# quadcopter.net
KiCad netlist of a schematic drawn in EAGLE
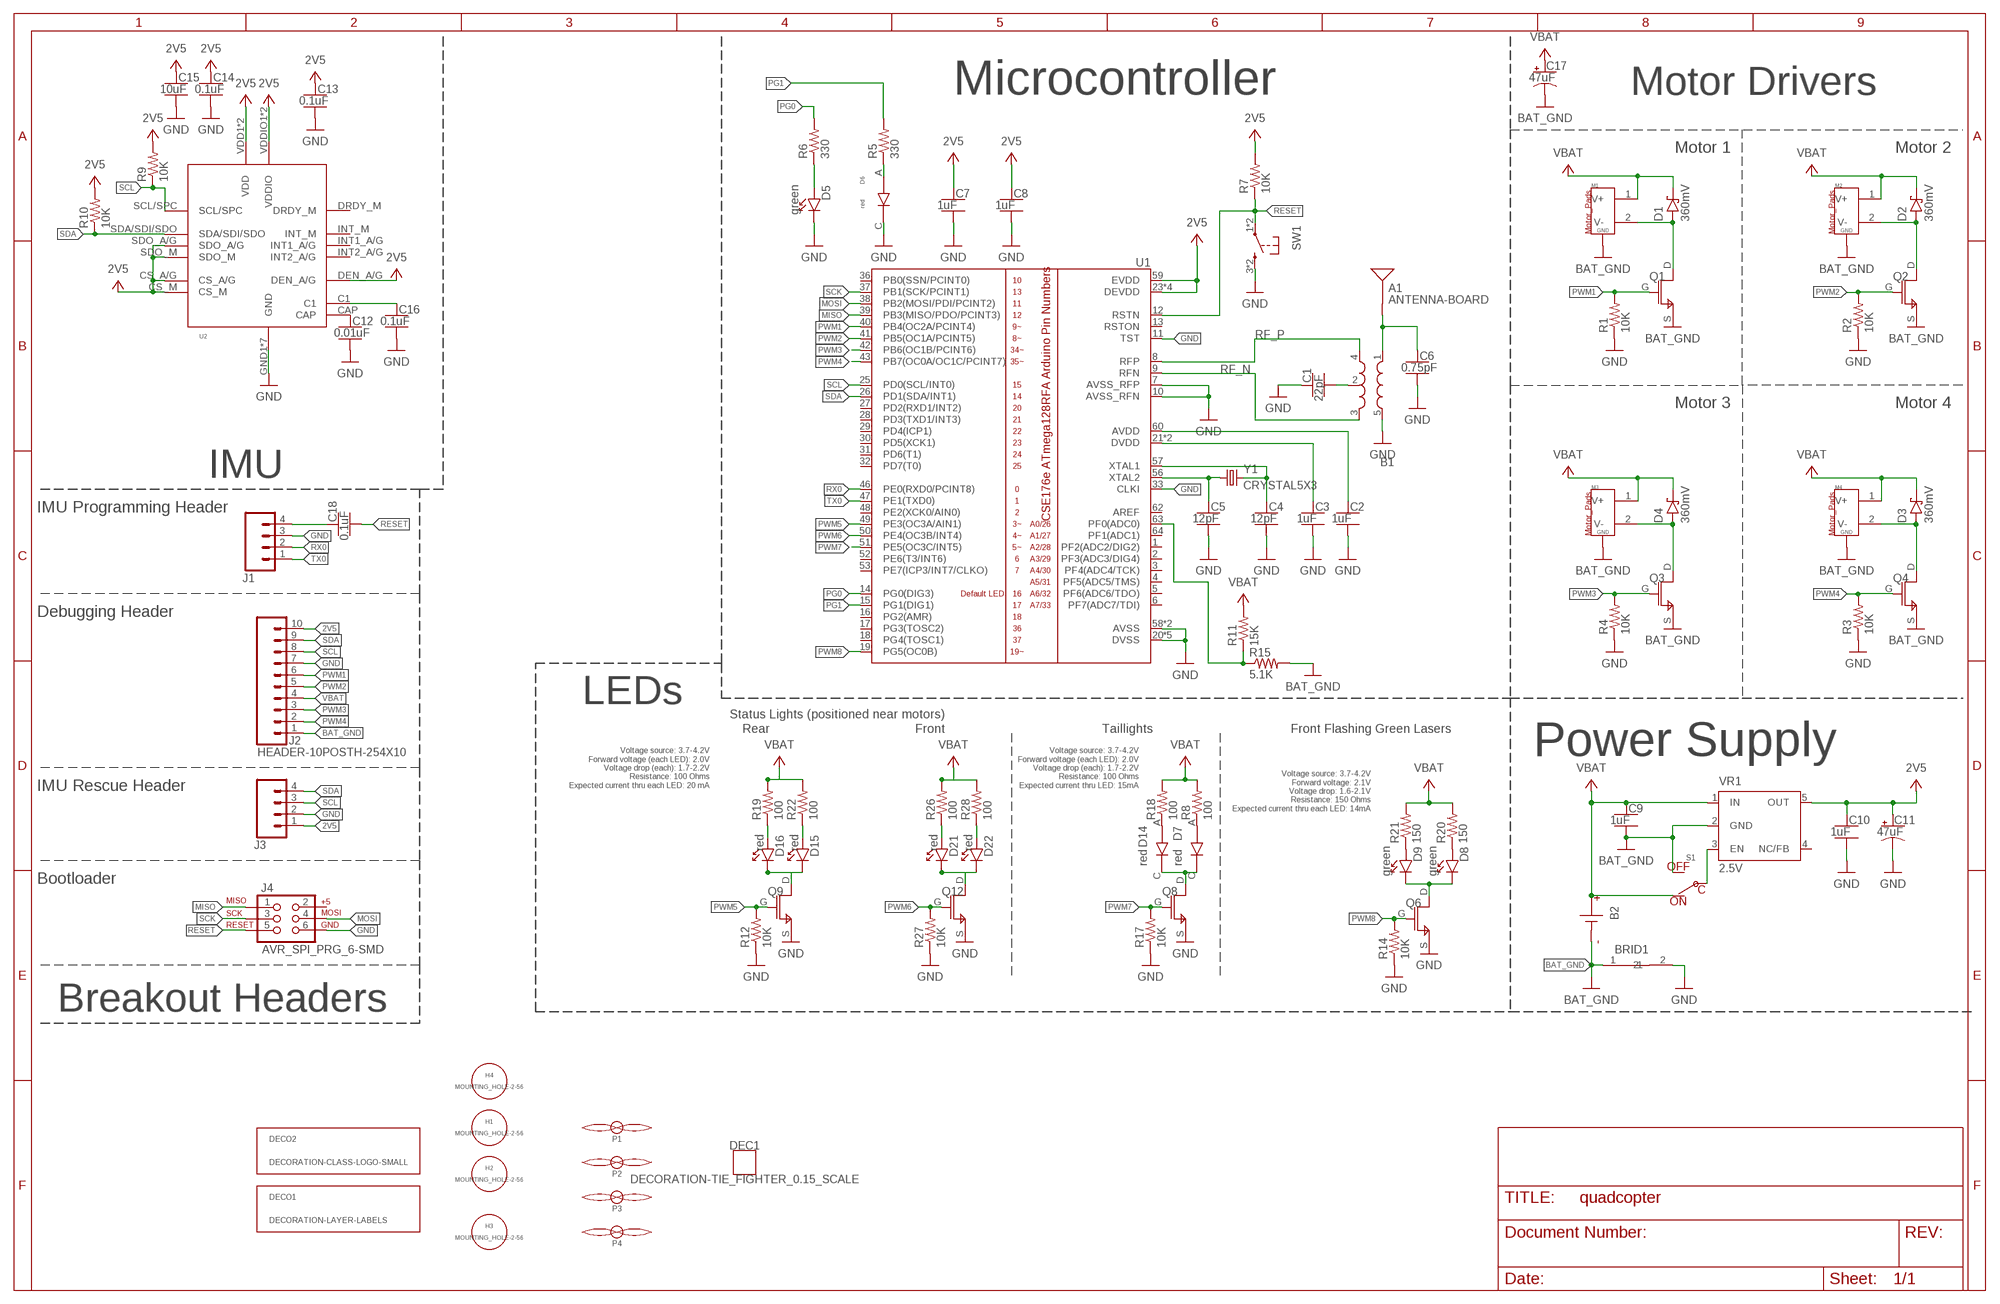
[diagram p0: schematic, sheet 1]

(export (version "E")
  (design (tool "Eeschema 10.0.6"))
  (components
    (comp (ref "A1")
      (value "ANTENNA-BOARD")
      (footprint "eagle-import:ANT_PCB_2.4GHZ_NRF8001_1.6MM_1OZ")
      (fields (field (name "MFR") "NA"))
      (libsource (lib "eagle-import") (part "ANTENNA-BOARD"))
    )
    (comp (ref "B1")
      (value "BALUN0805")
      (footprint "eagle-import:BALUN")
      (fields (field (name "MFR") "Wurth Electronics Inc.") (field (name "MPN") "748421245"))
      (libsource (lib "eagle-import") (part "BALUN0805"))
    )
    (comp (ref "B2")
      (value "BATTERY-SMD-TH")
      (footprint "eagle-import:BATTERY-COMBO")
      (libsource (lib "eagle-import") (part "BATTERY-SMD-TH"))
    )
    (comp (ref "BRID1")
      (value "NET_BRIDGE_5X5")
      (footprint "eagle-import:NET_BRIDGE_5X5")
      (libsource (lib "eagle-import") (part "NET_BRIDGE_5X5"))
    )
    (comp (ref "C1")
      (value "22pF")
      (footprint "eagle-import:CAPC2012X140_HS")
      (fields (field (name "MFR") "Murata Electronics") (field (name "MPN") "GRM21A5C2E220JW01D"))
      (libsource (lib "eagle-import") (part "CAPACITOR-NP_SMD-2012-0805_CERAMIC-22PF"))
    )
    (comp (ref "C2")
      (value "1uF")
      (footprint "eagle-import:CAPC2012X140_HS")
      (fields (field (name "MFR") "Taiyo Yuden") (field (name "MPN") "TMK212B7105KG-T"))
      (libsource (lib "eagle-import") (part "CAPACITOR-NP_SMD-2012-0805_CERAMIC-1UF"))
    )
    (comp (ref "C3")
      (value "1uF")
      (footprint "eagle-import:CAPC2012X140_HS")
      (fields (field (name "MFR") "Taiyo Yuden") (field (name "MPN") "TMK212B7105KG-T"))
      (libsource (lib "eagle-import") (part "CAPACITOR-NP_SMD-2012-0805_CERAMIC-1UF"))
    )
    (comp (ref "C4")
      (value "12pF")
      (footprint "eagle-import:CAPC2012X140_HS")
      (fields (field (name "MFR") "Murata Electronics") (field (name "MPN") "GRM21A5C2E120JW01D"))
      (libsource (lib "eagle-import") (part "CAPACITOR-NP_SMD-2012-0805_CERAMIC-12PF"))
    )
    (comp (ref "C5")
      (value "12pF")
      (footprint "eagle-import:CAPC2012X140_HS")
      (fields (field (name "MFR") "Murata Electronics") (field (name "MPN") "GRM21A5C2E120JW01D"))
      (libsource (lib "eagle-import") (part "CAPACITOR-NP_SMD-2012-0805_CERAMIC-12PF"))
    )
    (comp (ref "C6")
      (value "0.75pF")
      (footprint "eagle-import:CAPC2012X140_HS")
      (fields (field (name "MFR") "Murata Electronics") (field (name "MPN") "GQM2195C2AR75CB01D"))
      (libsource (lib "eagle-import") (part "CAPACITOR-NP_SMD-2012-0805_CERAMIC-0.75PF"))
    )
    (comp (ref "C7")
      (value "1uF")
      (footprint "eagle-import:CAPC2012X140_HS")
      (fields (field (name "MFR") "Taiyo Yuden") (field (name "MPN") "TMK212B7105KG-T"))
      (libsource (lib "eagle-import") (part "CAPACITOR-NP_SMD-2012-0805_CERAMIC-1UF"))
    )
    (comp (ref "C8")
      (value "1uF")
      (footprint "eagle-import:CAPC2012X140_HS")
      (fields (field (name "MFR") "Taiyo Yuden") (field (name "MPN") "TMK212B7105KG-T"))
      (libsource (lib "eagle-import") (part "CAPACITOR-NP_SMD-2012-0805_CERAMIC-1UF"))
    )
    (comp (ref "C9")
      (value "1uF")
      (footprint "eagle-import:CAPC2012X140_HS")
      (fields (field (name "MFR") "Taiyo Yuden") (field (name "MPN") "TMK212B7105KG-T"))
      (libsource (lib "eagle-import") (part "CAPACITOR-NP_SMD-2012-0805_CERAMIC-1UF"))
    )
    (comp (ref "C10")
      (value "1uF")
      (footprint "eagle-import:CAPC2012X140_HS")
      (fields (field (name "MFR") "Taiyo Yuden") (field (name "MPN") "TMK212B7105KG-T"))
      (libsource (lib "eagle-import") (part "CAPACITOR-NP_SMD-2012-0805_CERAMIC-1UF"))
    )
    (comp (ref "C11")
      (value "47uF")
      (footprint "eagle-import:CAPMP3216X180")
      (fields (field (name "MFR") "AVX Corporation") (field (name "MPN") "TAJA476K006SNJV"))
      (libsource (lib "eagle-import") (part "CAPACITOR-POL_47UF-SMD-1206-TAJA"))
    )
    (comp (ref "C12")
      (value "0.01uF")
      (footprint "eagle-import:CAPC2012X140_HS")
      (fields (field (name "MFR") "Knowles Syfer") (field (name "MPN") "0805J0500104KJT"))
      (libsource (lib "eagle-import") (part "CAPACITOR-NP_SMD-2012-0805_CERAMIC-0.01UF"))
    )
    (comp (ref "C13")
      (value "0.1uF")
      (footprint "eagle-import:CAPC2012X140_HS")
      (fields (field (name "MFR") "TDK Corporation") (field (name "MPN") "C2012X7R2A104K125AA"))
      (libsource (lib "eagle-import") (part "CAPACITOR-NP_SMD-2012-0805_CERAMIC-0.1UF"))
    )
    (comp (ref "C14")
      (value "0.1uF")
      (footprint "eagle-import:CAPC2012X140_HS")
      (fields (field (name "MFR") "TDK Corporation") (field (name "MPN") "C2012X7R2A104K125AA"))
      (libsource (lib "eagle-import") (part "CAPACITOR-NP_SMD-2012-0805_CERAMIC-0.1UF"))
    )
    (comp (ref "C15")
      (value "10uF")
      (footprint "eagle-import:CAPC2012X140_HS")
      (fields (field (name "MFR") "TDK") (field (name "MPN") "C2012X5R1E106K125AB"))
      (libsource (lib "eagle-import") (part "CAPACITOR-NP_SMD-2012-0805_CERAMIC-10UF"))
    )
    (comp (ref "C16")
      (value "0.1uF")
      (footprint "eagle-import:CAPC2012X140_HS")
      (fields (field (name "MFR") "TDK Corporation") (field (name "MPN") "C2012X7R2A104K125AA"))
      (libsource (lib "eagle-import") (part "CAPACITOR-NP_SMD-2012-0805_CERAMIC-0.1UF"))
    )
    (comp (ref "C17")
      (value "47uF")
      (footprint "eagle-import:CAPMP3216X180")
      (fields (field (name "MFR") "AVX Corporation") (field (name "MPN") "TAJA476K006SNJV"))
      (libsource (lib "eagle-import") (part "CAPACITOR-POL_47UF-SMD-1206-TAJA"))
    )
    (comp (ref "C18")
      (value "0.1uF")
      (footprint "eagle-import:CAPC2012X140_HS")
      (fields (field (name "MFR") "TDK Corporation") (field (name "MPN") "C2012X7R2A104K125AA"))
      (libsource (lib "eagle-import") (part "CAPACITOR-NP_SMD-2012-0805_CERAMIC-0.1UF"))
    )
    (comp (ref "D1")
      (value "360mV")
      (footprint "eagle-import:SODFL3516X96")
      (fields
        (field (name "MFR") "Toshiba Semiconductor and Storage")
        (field (name "MPN") "CRS08(TE85L,Q,M)")
      )
      (libsource (lib "eagle-import") (part "DIODE-SCHOTTKY_-SMD-SOD123"))
    )
    (comp (ref "D2")
      (value "360mV")
      (footprint "eagle-import:SODFL3516X96")
      (fields
        (field (name "MFR") "Toshiba Semiconductor and Storage")
        (field (name "MPN") "CRS08(TE85L,Q,M)")
      )
      (libsource (lib "eagle-import") (part "DIODE-SCHOTTKY_-SMD-SOD123"))
    )
    (comp (ref "D3")
      (value "360mV")
      (footprint "eagle-import:SODFL3516X96")
      (fields
        (field (name "MFR") "Toshiba Semiconductor and Storage")
        (field (name "MPN") "CRS08(TE85L,Q,M)")
      )
      (libsource (lib "eagle-import") (part "DIODE-SCHOTTKY_-SMD-SOD123"))
    )
    (comp (ref "D4")
      (value "360mV")
      (footprint "eagle-import:SODFL3516X96")
      (fields
        (field (name "MFR") "Toshiba Semiconductor and Storage")
        (field (name "MPN") "CRS08(TE85L,Q,M)")
      )
      (libsource (lib "eagle-import") (part "DIODE-SCHOTTKY_-SMD-SOD123"))
    )
    (comp (ref "D5")
      (value "green")
      (footprint "eagle-import:LEDSC125X200X120-2_HS")
      (fields (field (name "MFR") "Lite-On Inc") (field (name "MPN") "LTST-C170GKT"))
      (libsource (lib "eagle-import") (part "DIODE-LED_SMD-2012-0805-GREEN"))
    )
    (comp (ref "D6")
      (value "red")
      (footprint "eagle-import:LTST-C170EKT")
      (libsource (lib "eagle-import") (part "LED_RED-LTST-C170EKT"))
    )
    (comp (ref "D7")
      (value "red")
      (footprint "eagle-import:LTST-C170EKT")
      (libsource (lib "eagle-import") (part "LED_RED-LTST-C170EKT"))
    )
    (comp (ref "D8")
      (value "green")
      (footprint "eagle-import:LEDSC125X200X120-2_HS")
      (fields (field (name "MFR") "Lite-On Inc") (field (name "MPN") "LTST-C170GKT"))
      (libsource (lib "eagle-import") (part "DIODE-LED_SMD-2012-0805-GREEN"))
    )
    (comp (ref "D9")
      (value "green")
      (footprint "eagle-import:LEDSC125X200X120-2_HS")
      (fields (field (name "MFR") "Lite-On Inc") (field (name "MPN") "LTST-C170GKT"))
      (libsource (lib "eagle-import") (part "DIODE-LED_SMD-2012-0805-GREEN"))
    )
    (comp (ref "D14")
      (value "red")
      (footprint "eagle-import:LTST-C170EKT")
      (libsource (lib "eagle-import") (part "LED_RED-LTST-C170EKT"))
    )
    (comp (ref "D15")
      (value "red")
      (footprint "eagle-import:1206_LED_REVERSE")
      (libsource (lib "eagle-import") (part "LED-350-2312-1-ND-REVERSE"))
    )
    (comp (ref "D16")
      (value "red")
      (footprint "eagle-import:1206_LED_REVERSE")
      (libsource (lib "eagle-import") (part "LED-350-2312-1-ND-REVERSE"))
    )
    (comp (ref "D21")
      (value "red")
      (footprint "eagle-import:1206_LED_REVERSE")
      (libsource (lib "eagle-import") (part "LED-350-2312-1-ND-REVERSE"))
    )
    (comp (ref "D22")
      (value "red")
      (footprint "eagle-import:1206_LED_REVERSE")
      (libsource (lib "eagle-import") (part "LED-350-2312-1-ND-REVERSE"))
    )
    (comp (ref "DEC1")
      (value "DECORATION-TIE_FIGHTER_0.15_SCALE")
      (footprint "eagle-import:TIE_FIGHTER_0.15_SCALE")
      (libsource (lib "eagle-import") (part "DECORATION-TIE_FIGHTER_0.15_SCALE"))
    )
    (comp (ref "DECO1")
      (value "DECORATION-LAYER-LABELS")
      (footprint "eagle-import:LAYER_LABELS")
      (libsource (lib "eagle-import") (part "DECORATION-LAYER-LABELS"))
    )
    (comp (ref "DECO2")
      (value "DECORATION-CLASS-LOGO-SMALL")
      (footprint "eagle-import:QUADCLASS_LOGO_SMALL")
      (libsource (lib "eagle-import") (part "DECORATION-CLASS-LOGO-SMALL"))
    )
    (comp (ref "H1")
      (value "MOUNTING_HOLE-2-56")
      (footprint "eagle-import:2-56-MOUNTING-HOLE-NO-METAL")
      (libsource (lib "eagle-import") (part "MOUNTING_HOLE-2-56"))
    )
    (comp (ref "H2")
      (value "MOUNTING_HOLE-2-56")
      (footprint "eagle-import:2-56-MOUNTING-HOLE-NO-METAL")
      (libsource (lib "eagle-import") (part "MOUNTING_HOLE-2-56"))
    )
    (comp (ref "H3")
      (value "MOUNTING_HOLE-2-56")
      (footprint "eagle-import:2-56-MOUNTING-HOLE-NO-METAL")
      (libsource (lib "eagle-import") (part "MOUNTING_HOLE-2-56"))
    )
    (comp (ref "H4")
      (value "MOUNTING_HOLE-2-56")
      (footprint "eagle-import:2-56-MOUNTING-HOLE-NO-METAL")
      (libsource (lib "eagle-import") (part "MOUNTING_HOLE-2-56"))
    )
    (comp (ref "J1")
      (value "HEADER-4POS-0.1IN-FEMALE-SMD-BOTTOM-ENTRY")
      (footprint "eagle-import:HEADER-1X4-BOTTOM-ENTRY")
      (fields (field (name "MFR") "TE Connectivity AMP Connectors") (field (name "MPN") "1241152-4"))
      (libsource (lib "eagle-import") (part "HEADER-4POS-0.1IN-FEMALE-SMD-BOTTOM-ENTRY"))
    )
    (comp (ref "J2")
      (value "HEADER-10POSTH-254X10")
      (footprint "eagle-import:HDRV10W63P254_10X1_2540X254H838_HS")
      (fields (field (name "MFR") "Amphenol FCI") (field (name "MPN") "68000-110HLF"))
      (libsource (lib "eagle-import") (part "HEADER-10POSTH-254X10"))
    )
    (comp (ref "J3")
      (value "HEADER-4POS-0.1IN-FEMALE")
      (footprint "eagle-import:HDRVR4W80P254_1X4_1066X254X850B")
      (libsource (lib "eagle-import") (part "HEADER-4POS-0.1IN-FEMALE"))
    )
    (comp (ref "J4")
      (value "AVR_SPI_PRG_6-SMD")
      (footprint "eagle-import:2X3-SMD")
      (fields (field (name "MFR") "Amphenol ICC (FCI)") (field (name "MPN") "95278-101A06LF"))
      (libsource (lib "eagle-import") (part "AVR_SPI_PRG_6-SMD"))
    )
    (comp (ref "M1")
      (value "MOTOR_PADS_GND-MOLEX-SMD")
      (footprint "eagle-import:MOLEX-0532610271")
      (fields (field (name "MFR") "Molex") (field (name "MPN") "532610271"))
      (libsource (lib "eagle-import") (part "MOTOR_PADS_GND-MOLEX-SMD"))
    )
    (comp (ref "M2")
      (value "MOTOR_PADS_GND-MOLEX-SMD")
      (footprint "eagle-import:MOLEX-0532610271")
      (fields (field (name "MFR") "Molex") (field (name "MPN") "532610271"))
      (libsource (lib "eagle-import") (part "MOTOR_PADS_GND-MOLEX-SMD"))
    )
    (comp (ref "M3")
      (value "MOTOR_PADS_GND-MOLEX-SMD")
      (footprint "eagle-import:MOLEX-0532610271")
      (fields (field (name "MFR") "Molex") (field (name "MPN") "532610271"))
      (libsource (lib "eagle-import") (part "MOTOR_PADS_GND-MOLEX-SMD"))
    )
    (comp (ref "M4")
      (value "MOTOR_PADS_GND-MOLEX-SMD")
      (footprint "eagle-import:MOLEX-0532610271")
      (fields (field (name "MFR") "Molex") (field (name "MPN") "532610271"))
      (libsource (lib "eagle-import") (part "MOTOR_PADS_GND-MOLEX-SMD"))
    )
    (comp (ref "P1")
      (value "PROPELLOR-45MM")
      (footprint "eagle-import:MOTOR_AND_PROP")
      (libsource (lib "eagle-import") (part "PROPELLOR-45MM"))
    )
    (comp (ref "P2")
      (value "PROPELLOR-45MM")
      (footprint "eagle-import:MOTOR_AND_PROP")
      (libsource (lib "eagle-import") (part "PROPELLOR-45MM"))
    )
    (comp (ref "P3")
      (value "PROPELLOR-45MM")
      (footprint "eagle-import:MOTOR_AND_PROP")
      (libsource (lib "eagle-import") (part "PROPELLOR-45MM"))
    )
    (comp (ref "P4")
      (value "PROPELLOR-45MM")
      (footprint "eagle-import:MOTOR_AND_PROP")
      (libsource (lib "eagle-import") (part "PROPELLOR-45MM"))
    )
    (comp (ref "Q1")
      (value "N-MOSFET-SI2302DS")
      (footprint "eagle-import:SI2302DS")
      (libsource (lib "eagle-import") (part "N-MOSFET-SI2302DS"))
    )
    (comp (ref "Q2")
      (value "N-MOSFET-SI2302DS")
      (footprint "eagle-import:SI2302DS")
      (libsource (lib "eagle-import") (part "N-MOSFET-SI2302DS"))
    )
    (comp (ref "Q3")
      (value "N-MOSFET-SI2302DS")
      (footprint "eagle-import:SI2302DS")
      (libsource (lib "eagle-import") (part "N-MOSFET-SI2302DS"))
    )
    (comp (ref "Q4")
      (value "N-MOSFET-SI2302DS")
      (footprint "eagle-import:SI2302DS")
      (libsource (lib "eagle-import") (part "N-MOSFET-SI2302DS"))
    )
    (comp (ref "Q6")
      (value "N-MOSFET-SI2302DS")
      (footprint "eagle-import:SI2302DS")
      (libsource (lib "eagle-import") (part "N-MOSFET-SI2302DS"))
    )
    (comp (ref "Q8")
      (value "N-MOSFET-SI2302DS")
      (footprint "eagle-import:SI2302DS")
      (libsource (lib "eagle-import") (part "N-MOSFET-SI2302DS"))
    )
    (comp (ref "Q9")
      (value "N-MOSFET-SI2302DS")
      (footprint "eagle-import:SI2302DS")
      (libsource (lib "eagle-import") (part "N-MOSFET-SI2302DS"))
    )
    (comp (ref "Q12")
      (value "N-MOSFET-SI2302DS")
      (footprint "eagle-import:SI2302DS")
      (libsource (lib "eagle-import") (part "N-MOSFET-SI2302DS"))
    )
    (comp (ref "R1")
      (value "10K")
      (footprint "eagle-import:RESC2012X60_HS")
      (fields (field (name "MFR") "Yageo") (field (name "MPN") "RC0805JR-0710KL"))
      (libsource (lib "eagle-import") (part "RESISTOR_SMD-2012-0805-10K"))
    )
    (comp (ref "R2")
      (value "10K")
      (footprint "eagle-import:RESC2012X60_HS")
      (fields (field (name "MFR") "Yageo") (field (name "MPN") "RC0805JR-0710KL"))
      (libsource (lib "eagle-import") (part "RESISTOR_SMD-2012-0805-10K"))
    )
    (comp (ref "R3")
      (value "10K")
      (footprint "eagle-import:RESC2012X60_HS")
      (fields (field (name "MFR") "Yageo") (field (name "MPN") "RC0805JR-0710KL"))
      (libsource (lib "eagle-import") (part "RESISTOR_SMD-2012-0805-10K"))
    )
    (comp (ref "R4")
      (value "10K")
      (footprint "eagle-import:RESC2012X60_HS")
      (fields (field (name "MFR") "Yageo") (field (name "MPN") "RC0805JR-0710KL"))
      (libsource (lib "eagle-import") (part "RESISTOR_SMD-2012-0805-10K"))
    )
    (comp (ref "R5")
      (value "330")
      (footprint "eagle-import:RESC2012X60_HS")
      (fields (field (name "MFR") "Yageo") (field (name "MPN") "RC0805JR-07330RL"))
      (libsource (lib "eagle-import") (part "RESISTOR_SMD-2012-0805-330"))
    )
    (comp (ref "R6")
      (value "330")
      (footprint "eagle-import:RESC2012X60_HS")
      (fields (field (name "MFR") "Yageo") (field (name "MPN") "RC0805JR-07330RL"))
      (libsource (lib "eagle-import") (part "RESISTOR_SMD-2012-0805-330"))
    )
    (comp (ref "R7")
      (value "10K")
      (footprint "eagle-import:RESC2012X60_HS")
      (fields (field (name "MFR") "Yageo") (field (name "MPN") "RC0805JR-0710KL"))
      (libsource (lib "eagle-import") (part "RESISTOR_SMD-2012-0805-10K"))
    )
    (comp (ref "R8")
      (value "100")
      (footprint "eagle-import:RESC2012X60_HS")
      (fields (field (name "MFR") "Yageo") (field (name "MPN") "RC0805JR-07100RL"))
      (libsource (lib "eagle-import") (part "RESISTOR_SMD-2012-0805-100"))
    )
    (comp (ref "R9")
      (value "10K")
      (footprint "eagle-import:RESC2012X60_HS")
      (fields (field (name "MFR") "Yageo") (field (name "MPN") "RC0805JR-0710KL"))
      (libsource (lib "eagle-import") (part "RESISTOR_SMD-2012-0805-10K"))
    )
    (comp (ref "R10")
      (value "10K")
      (footprint "eagle-import:RESC2012X60_HS")
      (fields (field (name "MFR") "Yageo") (field (name "MPN") "RC0805JR-0710KL"))
      (libsource (lib "eagle-import") (part "RESISTOR_SMD-2012-0805-10K"))
    )
    (comp (ref "R11")
      (value "15K")
      (footprint "eagle-import:RESC2012X60_HS")
      (libsource (lib "eagle-import") (part "RESISTOR_SMD-2012-0805-15K"))
    )
    (comp (ref "R12")
      (value "10K")
      (footprint "eagle-import:RESC2012X60_HS")
      (fields (field (name "MFR") "Yageo") (field (name "MPN") "RC0805JR-0710KL"))
      (libsource (lib "eagle-import") (part "RESISTOR_SMD-2012-0805-10K"))
    )
    (comp (ref "R14")
      (value "10K")
      (footprint "eagle-import:RESC2012X60_HS")
      (fields (field (name "MFR") "Yageo") (field (name "MPN") "RC0805JR-0710KL"))
      (libsource (lib "eagle-import") (part "RESISTOR_SMD-2012-0805-10K"))
    )
    (comp (ref "R15")
      (value "5.1K")
      (footprint "eagle-import:RESC2012X60_HS")
      (fields (field (name "MFR") "Yageo") (field (name "MPN") "RC0805JR-075K1L"))
      (libsource (lib "eagle-import") (part "RESISTOR_SMD-2012-0805-5.1K"))
    )
    (comp (ref "R17")
      (value "10K")
      (footprint "eagle-import:RESC2012X60_HS")
      (fields (field (name "MFR") "Yageo") (field (name "MPN") "RC0805JR-0710KL"))
      (libsource (lib "eagle-import") (part "RESISTOR_SMD-2012-0805-10K"))
    )
    (comp (ref "R18")
      (value "100")
      (footprint "eagle-import:RESC2012X60_HS")
      (fields (field (name "MFR") "Yageo") (field (name "MPN") "RC0805JR-07100RL"))
      (libsource (lib "eagle-import") (part "RESISTOR_SMD-2012-0805-100"))
    )
    (comp (ref "R19")
      (value "100")
      (footprint "eagle-import:RESC2012X60_HS")
      (fields (field (name "MFR") "Yageo") (field (name "MPN") "RC0805JR-07100RL"))
      (libsource (lib "eagle-import") (part "RESISTOR_SMD-2012-0805-100"))
    )
    (comp (ref "R20")
      (value "150")
      (footprint "eagle-import:RESC2012X60_HS")
      (libsource (lib "eagle-import") (part "RESISTOR_SMD-2012-0805-150"))
    )
    (comp (ref "R21")
      (value "150")
      (footprint "eagle-import:RESC2012X60_HS")
      (libsource (lib "eagle-import") (part "RESISTOR_SMD-2012-0805-150"))
    )
    (comp (ref "R22")
      (value "100")
      (footprint "eagle-import:RESC2012X60_HS")
      (fields (field (name "MFR") "Yageo") (field (name "MPN") "RC0805JR-07100RL"))
      (libsource (lib "eagle-import") (part "RESISTOR_SMD-2012-0805-100"))
    )
    (comp (ref "R26")
      (value "100")
      (footprint "eagle-import:RESC2012X60_HS")
      (fields (field (name "MFR") "Yageo") (field (name "MPN") "RC0805JR-07100RL"))
      (libsource (lib "eagle-import") (part "RESISTOR_SMD-2012-0805-100"))
    )
    (comp (ref "R27")
      (value "10K")
      (footprint "eagle-import:RESC2012X60_HS")
      (fields (field (name "MFR") "Yageo") (field (name "MPN") "RC0805JR-0710KL"))
      (libsource (lib "eagle-import") (part "RESISTOR_SMD-2012-0805-10K"))
    )
    (comp (ref "R28")
      (value "100")
      (footprint "eagle-import:RESC2012X60_HS")
      (fields (field (name "MFR") "Yageo") (field (name "MPN") "RC0805JR-07100RL"))
      (libsource (lib "eagle-import") (part "RESISTOR_SMD-2012-0805-100"))
    )
    (comp (ref "S1")
      (value "POWER-SWITCH-MFS201N-9-Z-SMD-EDGE")
      (footprint "eagle-import:JS102011SAQN")
      (fields (field (name "MFR") "C&K") (field (name "MPN") "JS102011SAQN"))
      (libsource (lib "eagle-import") (part "POWER-SWITCH-MFS201N-9-Z-SMD-EDGE"))
    )
    (comp (ref "SW1")
      (value "PUSHBUTTON_-4.5X4.5")
      (footprint "eagle-import:4.5MM_TACTILE_SWITCH_TL3305AF160QG")
      (fields (field (name "MFR") "E-Switch") (field (name "MPN") "TL3305AF160QG"))
      (libsource (lib "eagle-import") (part "PUSHBUTTON_-4.5X4.5"))
    )
    (comp (ref "U1")
      (value "ATMEGA128RFA1")
      (footprint "eagle-import:QFN-64")
      (fields (field (name "MFR") "Microchip Technology") (field (name "MPN") "ATMEGA128RFA1-ZU"))
      (libsource (lib "eagle-import") (part "ATMEGA128RFA1"))
    )
    (comp (ref "U2")
      (value "IMU_LSM9DS1-LSM9DS1")
      (footprint "eagle-import:LSM9DS1")
      (libsource (lib "eagle-import") (part "IMU_LSM9DS1-LSM9DS1"))
    )
    (comp (ref "VR1")
      (value "2.5V")
      (footprint "eagle-import:SOT23-DBV")
      (fields (field (name "MFR") "Texas Instruments") (field (name "MPN") "LP3985IM5X-2.5/NOPB"))
      (libsource (lib "eagle-import") (part "TPS73633-DBVT2.5V"))
    )
    (comp (ref "Y1")
      (value "CRYSTAL5X3")
      (footprint "eagle-import:CRYSTAL-SMD-5X3")
      (fields (field (name "MFR") "Abracon LLC") (field (name "MPN") "ABM3B-16.000MHZ-B2-T"))
      (libsource (lib "eagle-import") (part "CRYSTAL5X3"))
    )
  )
  (nets
    (net (code "1") (name "/RF_N") (class "Default")
      (node (ref "B1") (pin "3") (pinfunction "OUT2_3") (pintype "bidirectional"))
      (node (ref "U1") (pin "9") (pinfunction "RFN_9") (pintype "bidirectional"))
    )
    (net (code "2") (name "/RF_P") (class "Default")
      (node (ref "B1") (pin "4") (pinfunction "OUT1_4") (pintype "bidirectional"))
      (node (ref "U1") (pin "8") (pinfunction "RFP_8") (pintype "bidirectional"))
    )
    (net (code "3") (name "2V5") (class "Default")
      (node (ref "C10") (pin "1") (pinfunction "1_1") (pintype "passive"))
      (node (ref "C11") (pin "1") (pinfunction "+_1") (pintype "passive"))
      (node (ref "C13") (pin "1") (pinfunction "1_1") (pintype "passive"))
      (node (ref "C14") (pin "1") (pinfunction "1_1") (pintype "passive"))
      (node (ref "C15") (pin "1") (pinfunction "1_1") (pintype "passive"))
      (node (ref "C7") (pin "1") (pinfunction "1_1") (pintype "passive"))
      (node (ref "C8") (pin "1") (pinfunction "1_1") (pintype "passive"))
      (node (ref "J2") (pin "10") (pinfunction "10_10") (pintype "passive"))
      (node (ref "J3") (pin "1") (pinfunction "1_1") (pintype "bidirectional"))
      (node (ref "R10") (pin "2") (pinfunction "2_2") (pintype "passive"))
      (node (ref "R7") (pin "2") (pinfunction "2_2") (pintype "passive"))
      (node (ref "R9") (pin "2") (pinfunction "2_2") (pintype "passive"))
      (node (ref "U1") (pin "23") (pinfunction "DEVDD_23") (pintype "bidirectional"))
      (node (ref "U1") (pin "34") (pinfunction "DEVDD_34") (pintype "bidirectional"))
      (node (ref "U1") (pin "44") (pinfunction "DEVDD_44") (pintype "bidirectional"))
      (node (ref "U1") (pin "54") (pinfunction "DEVDD_54") (pintype "bidirectional"))
      (node (ref "U1") (pin "59") (pinfunction "EVDD_59") (pintype "bidirectional"))
      (node (ref "U2") (pin "CS_A/G") (pinfunction "CS_A/G_CS_A/G") (pintype "bidirectional"))
      (node (ref "U2") (pin "CS_M") (pinfunction "CS_M_CS_M") (pintype "bidirectional"))
      (node (ref "U2") (pin "DEN_A/G") (pinfunction "DEN_A/G_DEN_A/G") (pintype "bidirectional"))
      (node (ref "U2") (pin "SDO_A/G") (pinfunction "SDO_A/G_SDO_A/G") (pintype "bidirectional"))
      (node (ref "U2") (pin "SDO_M") (pinfunction "SDO_M_SDO_M") (pintype "bidirectional"))
      (node (ref "U2") (pin "VDD1") (pinfunction "VDD_VDD1") (pintype "bidirectional"))
      (node (ref "U2") (pin "VDD2") (pinfunction "VDD_VDD2") (pintype "bidirectional"))
      (node (ref "U2") (pin "VDDIO1") (pinfunction "VDDIO_VDDIO1") (pintype "bidirectional"))
      (node (ref "U2") (pin "VDDIO2") (pinfunction "VDDIO_VDDIO2") (pintype "bidirectional"))
      (node (ref "VR1") (pin "5") (pinfunction "OUT_5") (pintype "passive"))
    )
    (net (code "4") (name "BAT_GND") (class "Default")
      (node (ref "B2") (pin "2") (pinfunction "N_2") (pintype "bidirectional"))
      (node (ref "B2") (pin "G") (pinfunction "N_G") (pintype "bidirectional"))
      (node (ref "B2") (pin "G2") (pinfunction "N_G2") (pintype "bidirectional"))
      (node (ref "B2") (pin "G3") (pinfunction "N_G3") (pintype "bidirectional"))
      (node (ref "BRID1") (pin "1") (pinfunction "1_1") (pintype "bidirectional"))
      (node (ref "C17") (pin "2") (pinfunction "-_2") (pintype "passive"))
      (node (ref "C9") (pin "2") (pinfunction "2_2") (pintype "passive"))
      (node (ref "J2") (pin "1") (pinfunction "1_1") (pintype "passive"))
      (node (ref "M1") (pin "G1") (pinfunction "GND_G1") (pintype "bidirectional"))
      (node (ref "M1") (pin "G2") (pinfunction "GND_G2") (pintype "bidirectional"))
      (node (ref "M2") (pin "G1") (pinfunction "GND_G1") (pintype "bidirectional"))
      (node (ref "M2") (pin "G2") (pinfunction "GND_G2") (pintype "bidirectional"))
      (node (ref "M3") (pin "G1") (pinfunction "GND_G1") (pintype "bidirectional"))
      (node (ref "M3") (pin "G2") (pinfunction "GND_G2") (pintype "bidirectional"))
      (node (ref "M4") (pin "G1") (pinfunction "GND_G1") (pintype "bidirectional"))
      (node (ref "M4") (pin "G2") (pinfunction "GND_G2") (pintype "bidirectional"))
      (node (ref "Q1") (pin "S") (pinfunction "S_S") (pintype "bidirectional"))
      (node (ref "Q2") (pin "S") (pinfunction "S_S") (pintype "bidirectional"))
      (node (ref "Q3") (pin "S") (pinfunction "S_S") (pintype "bidirectional"))
      (node (ref "Q4") (pin "S") (pinfunction "S_S") (pintype "bidirectional"))
      (node (ref "R15") (pin "2") (pinfunction "2_2") (pintype "passive"))
      (node (ref "S1") (pin "A") (pinfunction "OFF_A") (pintype "bidirectional"))
      (node (ref "VR1") (pin "2") (pinfunction "GND_2") (pintype "input"))
    )
    (net (code "5") (name "GND") (class "Default")
      (node (ref "B1") (pin "5") (pinfunction "GND_5") (pintype "bidirectional"))
      (node (ref "BRID1") (pin "2") (pinfunction "2_2") (pintype "bidirectional"))
      (node (ref "C1") (pin "1") (pinfunction "1_1") (pintype "passive"))
      (node (ref "C10") (pin "2") (pinfunction "2_2") (pintype "passive"))
      (node (ref "C11") (pin "2") (pinfunction "-_2") (pintype "passive"))
      (node (ref "C12") (pin "2") (pinfunction "2_2") (pintype "passive"))
      (node (ref "C13") (pin "2") (pinfunction "2_2") (pintype "passive"))
      (node (ref "C14") (pin "2") (pinfunction "2_2") (pintype "passive"))
      (node (ref "C15") (pin "2") (pinfunction "2_2") (pintype "passive"))
      (node (ref "C16") (pin "2") (pinfunction "2_2") (pintype "passive"))
      (node (ref "C2") (pin "2") (pinfunction "2_2") (pintype "passive"))
      (node (ref "C3") (pin "2") (pinfunction "2_2") (pintype "passive"))
      (node (ref "C4") (pin "2") (pinfunction "2_2") (pintype "passive"))
      (node (ref "C5") (pin "2") (pinfunction "2_2") (pintype "passive"))
      (node (ref "C6") (pin "2") (pinfunction "2_2") (pintype "passive"))
      (node (ref "C7") (pin "2") (pinfunction "2_2") (pintype "passive"))
      (node (ref "C8") (pin "2") (pinfunction "2_2") (pintype "passive"))
      (node (ref "D5") (pin "C") (pinfunction "C_C") (pintype "passive"))
      (node (ref "D6") (pin "C") (pinfunction "C_C") (pintype "bidirectional"))
      (node (ref "J1") (pin "3") (pinfunction "3_3") (pintype "bidirectional"))
      (node (ref "J2") (pin "7") (pinfunction "7_7") (pintype "passive"))
      (node (ref "J3") (pin "2") (pinfunction "2_2") (pintype "bidirectional"))
      (node (ref "J4") (pin "6") (pinfunction "6_6") (pintype "passive"))
      (node (ref "Q12") (pin "S") (pinfunction "S_S") (pintype "bidirectional"))
      (node (ref "Q6") (pin "S") (pinfunction "S_S") (pintype "bidirectional"))
      (node (ref "Q8") (pin "S") (pinfunction "S_S") (pintype "bidirectional"))
      (node (ref "Q9") (pin "S") (pinfunction "S_S") (pintype "bidirectional"))
      (node (ref "R1") (pin "1") (pinfunction "1_1") (pintype "passive"))
      (node (ref "R12") (pin "1") (pinfunction "1_1") (pintype "passive"))
      (node (ref "R14") (pin "1") (pinfunction "1_1") (pintype "passive"))
      (node (ref "R17") (pin "1") (pinfunction "1_1") (pintype "passive"))
      (node (ref "R2") (pin "1") (pinfunction "1_1") (pintype "passive"))
      (node (ref "R27") (pin "1") (pinfunction "1_1") (pintype "passive"))
      (node (ref "R3") (pin "1") (pinfunction "1_1") (pintype "passive"))
      (node (ref "R4") (pin "1") (pinfunction "1_1") (pintype "passive"))
      (node (ref "SW1") (pin "3") (pinfunction "2_3") (pintype "passive"))
      (node (ref "SW1") (pin "4") (pinfunction "2_4") (pintype "passive"))
      (node (ref "U1") (pin "10") (pinfunction "AVSS_RFN_10") (pintype "bidirectional"))
      (node (ref "U1") (pin "11") (pinfunction "TST_11") (pintype "bidirectional"))
      (node (ref "U1") (pin "20") (pinfunction "DVSS_20") (pintype "bidirectional"))
      (node (ref "U1") (pin "24") (pinfunction "DVSS_24") (pintype "bidirectional"))
      (node (ref "U1") (pin "33") (pinfunction "CLKI_33") (pintype "bidirectional"))
      (node (ref "U1") (pin "35") (pinfunction "DVSS_35") (pintype "bidirectional"))
      (node (ref "U1") (pin "45") (pinfunction "DVSS_45") (pintype "bidirectional"))
      (node (ref "U1") (pin "55") (pinfunction "DVSS_55") (pintype "bidirectional"))
      (node (ref "U1") (pin "58") (pinfunction "AVSS_58") (pintype "bidirectional"))
      (node (ref "U1") (pin "61") (pinfunction "AVSS_61") (pintype "bidirectional"))
      (node (ref "U1") (pin "7") (pinfunction "AVSS_RFP_7") (pintype "bidirectional"))
      (node (ref "U2") (pin "GND1") (pinfunction "GND_GND1") (pintype "bidirectional"))
      (node (ref "U2") (pin "GND2") (pinfunction "GND_GND2") (pintype "bidirectional"))
      (node (ref "U2") (pin "RES1") (pinfunction "GND_RES1") (pintype "bidirectional"))
      (node (ref "U2") (pin "RES2") (pinfunction "GND_RES2") (pintype "bidirectional"))
      (node (ref "U2") (pin "RES3") (pinfunction "GND_RES3") (pintype "bidirectional"))
      (node (ref "U2") (pin "RES4") (pinfunction "GND_RES4") (pintype "bidirectional"))
      (node (ref "U2") (pin "RES5") (pinfunction "GND_RES5") (pintype "bidirectional"))
    )
    (net (code "6") (name "MISO") (class "Default")
      (node (ref "J4") (pin "1") (pinfunction "1_1") (pintype "passive"))
      (node (ref "U1") (pin "39") (pinfunction "PB3(MISO/PDO/PCINT3)_39") (pintype "bidirectional"))
    )
    (net (code "7") (name "MOSI") (class "Default")
      (node (ref "J4") (pin "4") (pinfunction "4_4") (pintype "passive"))
      (node (ref "U1") (pin "38") (pinfunction "PB2(MOSI/PDI/PCINT2)_38") (pintype "bidirectional"))
    )
    (net (code "8") (name "Net-(A1-SIGNAL)") (class "Default")
      (node (ref "A1") (pin "FEED") (pinfunction "SIGNAL_FEED") (pintype "bidirectional"))
      (node (ref "B1") (pin "1") (pinfunction "IN_1") (pintype "bidirectional"))
      (node (ref "C6") (pin "1") (pinfunction "1_1") (pintype "passive"))
    )
    (net (code "9") (name "Net-(B1-GND-Pad2)") (class "Default")
      (node (ref "B1") (pin "2") (pinfunction "GND_2") (pintype "bidirectional"))
      (node (ref "C1") (pin "2") (pinfunction "2_2") (pintype "passive"))
    )
    (net (code "10") (name "Net-(C3-Pad1)") (class "Default")
      (node (ref "C3") (pin "1") (pinfunction "1_1") (pintype "passive"))
      (node (ref "U1") (pin "21") (pinfunction "DVDD_21") (pintype "bidirectional"))
      (node (ref "U1") (pin "22") (pinfunction "DVDD_22") (pintype "bidirectional"))
    )
    (net (code "11") (name "Net-(C12-Pad1)") (class "Default")
      (node (ref "C12") (pin "1") (pinfunction "1_1") (pintype "passive"))
      (node (ref "U2") (pin "CAP") (pinfunction "CAP_CAP") (pintype "bidirectional"))
    )
    (net (code "12") (name "Net-(C16-Pad1)") (class "Default")
      (node (ref "C16") (pin "1") (pinfunction "1_1") (pintype "passive"))
      (node (ref "U2") (pin "C1") (pinfunction "C1_C1") (pintype "bidirectional"))
    )
    (net (code "13") (name "Net-(C18-Pad1)") (class "Default")
      (node (ref "C18") (pin "1") (pinfunction "1_1") (pintype "passive"))
      (node (ref "J1") (pin "4") (pinfunction "4_4") (pintype "bidirectional"))
    )
    (net (code "14") (name "Net-(D1-A)") (class "Default")
      (node (ref "D1") (pin "2") (pinfunction "A_2") (pintype "passive"))
      (node (ref "M1") (pin "2") (pinfunction "V-_2") (pintype "bidirectional"))
      (node (ref "Q1") (pin "D") (pinfunction "D_D") (pintype "bidirectional"))
    )
    (net (code "15") (name "Net-(D2-A)") (class "Default")
      (node (ref "D2") (pin "2") (pinfunction "A_2") (pintype "passive"))
      (node (ref "M2") (pin "2") (pinfunction "V-_2") (pintype "bidirectional"))
      (node (ref "Q2") (pin "D") (pinfunction "D_D") (pintype "bidirectional"))
    )
    (net (code "16") (name "Net-(D3-A)") (class "Default")
      (node (ref "D3") (pin "2") (pinfunction "A_2") (pintype "passive"))
      (node (ref "M4") (pin "2") (pinfunction "V-_2") (pintype "bidirectional"))
      (node (ref "Q4") (pin "D") (pinfunction "D_D") (pintype "bidirectional"))
    )
    (net (code "17") (name "Net-(D4-A)") (class "Default")
      (node (ref "D4") (pin "2") (pinfunction "A_2") (pintype "passive"))
      (node (ref "M3") (pin "2") (pinfunction "V-_2") (pintype "bidirectional"))
      (node (ref "Q3") (pin "D") (pinfunction "D_D") (pintype "bidirectional"))
    )
    (net (code "18") (name "Net-(D5-PadA)") (class "Default")
      (node (ref "D5") (pin "A") (pinfunction "A_A") (pintype "passive"))
      (node (ref "R6") (pin "1") (pinfunction "1_1") (pintype "passive"))
    )
    (net (code "19") (name "Net-(D6-PadA)") (class "Default")
      (node (ref "D6") (pin "A") (pinfunction "A_A") (pintype "bidirectional"))
      (node (ref "R5") (pin "1") (pinfunction "1_1") (pintype "passive"))
    )
    (net (code "20") (name "Net-(D7-PadA)") (class "Default")
      (node (ref "D7") (pin "A") (pinfunction "A_A") (pintype "bidirectional"))
      (node (ref "R8") (pin "1") (pinfunction "1_1") (pintype "passive"))
    )
    (net (code "21") (name "Net-(D8-PadA)") (class "Default")
      (node (ref "D8") (pin "A") (pinfunction "A_A") (pintype "passive"))
      (node (ref "R20") (pin "1") (pinfunction "1_1") (pintype "passive"))
    )
    (net (code "22") (name "Net-(D8-PadC)") (class "Default")
      (node (ref "D8") (pin "C") (pinfunction "C_C") (pintype "passive"))
      (node (ref "D9") (pin "C") (pinfunction "C_C") (pintype "passive"))
      (node (ref "Q6") (pin "D") (pinfunction "D_D") (pintype "bidirectional"))
    )
    (net (code "23") (name "Net-(D9-PadA)") (class "Default")
      (node (ref "D9") (pin "A") (pinfunction "A_A") (pintype "passive"))
      (node (ref "R21") (pin "1") (pinfunction "1_1") (pintype "passive"))
    )
    (net (code "24") (name "Net-(D14-PadA)") (class "Default")
      (node (ref "D14") (pin "A") (pinfunction "A_A") (pintype "bidirectional"))
      (node (ref "R18") (pin "1") (pinfunction "1_1") (pintype "passive"))
    )
    (net (code "25") (name "Net-(D14-PadC)") (class "Default")
      (node (ref "D14") (pin "C") (pinfunction "C_C") (pintype "bidirectional"))
      (node (ref "D7") (pin "C") (pinfunction "C_C") (pintype "bidirectional"))
      (node (ref "Q8") (pin "D") (pinfunction "D_D") (pintype "bidirectional"))
    )
    (net (code "26") (name "Net-(D15-A)") (class "Default")
      (node (ref "D15") (pin "2") (pinfunction "A_2") (pintype "passive"))
      (node (ref "R22") (pin "1") (pinfunction "1_1") (pintype "passive"))
    )
    (net (code "27") (name "Net-(D15-C)") (class "Default")
      (node (ref "D15") (pin "1") (pinfunction "C_1") (pintype "passive"))
      (node (ref "D16") (pin "1") (pinfunction "C_1") (pintype "passive"))
      (node (ref "Q9") (pin "D") (pinfunction "D_D") (pintype "bidirectional"))
    )
    (net (code "28") (name "Net-(D16-A)") (class "Default")
      (node (ref "D16") (pin "2") (pinfunction "A_2") (pintype "passive"))
      (node (ref "R19") (pin "1") (pinfunction "1_1") (pintype "passive"))
    )
    (net (code "29") (name "Net-(D21-A)") (class "Default")
      (node (ref "D21") (pin "2") (pinfunction "A_2") (pintype "passive"))
      (node (ref "R26") (pin "1") (pinfunction "1_1") (pintype "passive"))
    )
    (net (code "30") (name "Net-(D21-C)") (class "Default")
      (node (ref "D21") (pin "1") (pinfunction "C_1") (pintype "passive"))
      (node (ref "D22") (pin "1") (pinfunction "C_1") (pintype "passive"))
      (node (ref "Q12") (pin "D") (pinfunction "D_D") (pintype "bidirectional"))
    )
    (net (code "31") (name "Net-(D22-A)") (class "Default")
      (node (ref "D22") (pin "2") (pinfunction "A_2") (pintype "passive"))
      (node (ref "R28") (pin "1") (pinfunction "1_1") (pintype "passive"))
    )
    (net (code "32") (name "Net-(U1-AVDD)") (class "Default")
      (node (ref "C2") (pin "1") (pinfunction "1_1") (pintype "passive"))
      (node (ref "U1") (pin "60") (pinfunction "AVDD_60") (pintype "bidirectional"))
    )
    (net (code "33") (name "Net-(U1-PF0(ADC0))") (class "Default")
      (node (ref "R11") (pin "1") (pinfunction "1_1") (pintype "passive"))
      (node (ref "R15") (pin "1") (pinfunction "1_1") (pintype "passive"))
      (node (ref "U1") (pin "63") (pinfunction "PF0(ADC0)_63") (pintype "bidirectional"))
    )
    (net (code "34") (name "Net-(U1-XTAL1)") (class "Default")
      (node (ref "C4") (pin "1") (pinfunction "1_1") (pintype "passive"))
      (node (ref "U1") (pin "57") (pinfunction "XTAL1_57") (pintype "bidirectional"))
      (node (ref "Y1") (pin "3") (pinfunction "2_3") (pintype "passive"))
    )
    (net (code "35") (name "Net-(U1-XTAL2)") (class "Default")
      (node (ref "C5") (pin "1") (pinfunction "1_1") (pintype "passive"))
      (node (ref "U1") (pin "56") (pinfunction "XTAL2_56") (pintype "bidirectional"))
      (node (ref "Y1") (pin "1") (pinfunction "1_1") (pintype "passive"))
    )
    (net (code "36") (name "Net-(VR1-EN)") (class "Default")
      (node (ref "S1") (pin "C") (pinfunction "C_C") (pintype "bidirectional"))
      (node (ref "VR1") (pin "3") (pinfunction "EN_3") (pintype "input"))
    )
    (net (code "37") (name "PG0") (class "Default")
      (node (ref "R6") (pin "2") (pinfunction "2_2") (pintype "passive"))
      (node (ref "U1") (pin "14") (pinfunction "PG0(DIG3)_14") (pintype "bidirectional"))
    )
    (net (code "38") (name "PG1") (class "Default")
      (node (ref "R5") (pin "2") (pinfunction "2_2") (pintype "passive"))
      (node (ref "U1") (pin "15") (pinfunction "PG1(DIG1)_15") (pintype "bidirectional"))
    )
    (net (code "39") (name "PWM1") (class "Default")
      (node (ref "J2") (pin "6") (pinfunction "6_6") (pintype "passive"))
      (node (ref "Q1") (pin "G") (pinfunction "G_G") (pintype "bidirectional"))
      (node (ref "R1") (pin "2") (pinfunction "2_2") (pintype "passive"))
      (node (ref "U1") (pin "40") (pinfunction "PB4(OC2A/PCINT4)_40") (pintype "bidirectional"))
    )
    (net (code "40") (name "PWM2") (class "Default")
      (node (ref "J2") (pin "5") (pinfunction "5_5") (pintype "passive"))
      (node (ref "Q2") (pin "G") (pinfunction "G_G") (pintype "bidirectional"))
      (node (ref "R2") (pin "2") (pinfunction "2_2") (pintype "passive"))
      (node (ref "U1") (pin "41") (pinfunction "PB5(OC1A/PCINT5)_41") (pintype "bidirectional"))
    )
    (net (code "41") (name "PWM3") (class "Default")
      (node (ref "J2") (pin "3") (pinfunction "3_3") (pintype "passive"))
      (node (ref "Q3") (pin "G") (pinfunction "G_G") (pintype "bidirectional"))
      (node (ref "R4") (pin "2") (pinfunction "2_2") (pintype "passive"))
      (node (ref "U1") (pin "42") (pinfunction "PB6(OC1B/PCINT6)_42") (pintype "bidirectional"))
    )
    (net (code "42") (name "PWM4") (class "Default")
      (node (ref "J2") (pin "2") (pinfunction "2_2") (pintype "passive"))
      (node (ref "Q4") (pin "G") (pinfunction "G_G") (pintype "bidirectional"))
      (node (ref "R3") (pin "2") (pinfunction "2_2") (pintype "passive"))
      (node (ref "U1") (pin "43") (pinfunction "PB7(OC0A/OC1C/PCINT7)_43") (pintype "bidirectional"))
    )
    (net (code "43") (name "PWM5") (class "Default")
      (node (ref "Q9") (pin "G") (pinfunction "G_G") (pintype "bidirectional"))
      (node (ref "R12") (pin "2") (pinfunction "2_2") (pintype "passive"))
      (node (ref "U1") (pin "49") (pinfunction "PE3(OC3A/AIN1)_49") (pintype "bidirectional"))
    )
    (net (code "44") (name "PWM6") (class "Default")
      (node (ref "Q12") (pin "G") (pinfunction "G_G") (pintype "bidirectional"))
      (node (ref "R27") (pin "2") (pinfunction "2_2") (pintype "passive"))
      (node (ref "U1") (pin "50") (pinfunction "PE4(OC3B/INT4)_50") (pintype "bidirectional"))
    )
    (net (code "45") (name "PWM7") (class "Default")
      (node (ref "Q8") (pin "G") (pinfunction "G_G") (pintype "bidirectional"))
      (node (ref "R17") (pin "2") (pinfunction "2_2") (pintype "passive"))
      (node (ref "U1") (pin "51") (pinfunction "PE5(OC3C/INT5)_51") (pintype "bidirectional"))
    )
    (net (code "46") (name "PWM8") (class "Default")
      (node (ref "Q6") (pin "G") (pinfunction "G_G") (pintype "bidirectional"))
      (node (ref "R14") (pin "2") (pinfunction "2_2") (pintype "passive"))
      (node (ref "U1") (pin "19") (pinfunction "PG5(OC0B)_19") (pintype "bidirectional"))
    )
    (net (code "47") (name "RESET") (class "Default")
      (node (ref "C18") (pin "2") (pinfunction "2_2") (pintype "passive"))
      (node (ref "J4") (pin "5") (pinfunction "5_5") (pintype "passive"))
      (node (ref "R7") (pin "1") (pinfunction "1_1") (pintype "passive"))
      (node (ref "SW1") (pin "1") (pinfunction "1_1") (pintype "passive"))
      (node (ref "SW1") (pin "2") (pinfunction "1_2") (pintype "passive"))
      (node (ref "U1") (pin "12") (pinfunction "RSTN_12") (pintype "bidirectional"))
    )
    (net (code "48") (name "RX0") (class "Default")
      (node (ref "J1") (pin "2") (pinfunction "2_2") (pintype "bidirectional"))
      (node (ref "U1") (pin "46") (pinfunction "PE0(RXD0/PCINT8)_46") (pintype "bidirectional"))
    )
    (net (code "49") (name "SCK") (class "Default")
      (node (ref "J4") (pin "3") (pinfunction "3_3") (pintype "passive"))
      (node (ref "U1") (pin "37") (pinfunction "PB1(SCK/PCINT1)_37") (pintype "bidirectional"))
    )
    (net (code "50") (name "SCL") (class "Default")
      (node (ref "J2") (pin "8") (pinfunction "8_8") (pintype "passive"))
      (node (ref "J3") (pin "3") (pinfunction "3_3") (pintype "bidirectional"))
      (node (ref "R9") (pin "1") (pinfunction "1_1") (pintype "passive"))
      (node (ref "U1") (pin "25") (pinfunction "PD0(SCL/INT0)_25") (pintype "bidirectional"))
      (node (ref "U2") (pin "SCL/SPC") (pinfunction "SCL/SPC_SCL/SPC") (pintype "bidirectional"))
    )
    (net (code "51") (name "SDA") (class "Default")
      (node (ref "J2") (pin "9") (pinfunction "9_9") (pintype "passive"))
      (node (ref "J3") (pin "4") (pinfunction "4_4") (pintype "bidirectional"))
      (node (ref "R10") (pin "1") (pinfunction "1_1") (pintype "passive"))
      (node (ref "U1") (pin "26") (pinfunction "PD1(SDA/INT1)_26") (pintype "bidirectional"))
      (node (ref "U2") (pin "SDA/SDI/SDO") (pinfunction "SDA/SDI/SDO_SDA/SDI/SDO") (pintype "bidirectional"))
    )
    (net (code "52") (name "TX0") (class "Default")
      (node (ref "J1") (pin "1") (pinfunction "1_1") (pintype "bidirectional"))
      (node (ref "U1") (pin "47") (pinfunction "PE1(TXD0)_47") (pintype "bidirectional"))
    )
    (net (code "53") (name "VBAT") (class "Default")
      (node (ref "B2") (pin "1") (pinfunction "P_1") (pintype "bidirectional"))
      (node (ref "B2") (pin "P") (pinfunction "P_P") (pintype "bidirectional"))
      (node (ref "C17") (pin "1") (pinfunction "+_1") (pintype "passive"))
      (node (ref "C9") (pin "1") (pinfunction "1_1") (pintype "passive"))
      (node (ref "D1") (pin "1") (pinfunction "C_1") (pintype "passive"))
      (node (ref "D2") (pin "1") (pinfunction "C_1") (pintype "passive"))
      (node (ref "D3") (pin "1") (pinfunction "C_1") (pintype "passive"))
      (node (ref "D4") (pin "1") (pinfunction "C_1") (pintype "passive"))
      (node (ref "J2") (pin "4") (pinfunction "4_4") (pintype "passive"))
      (node (ref "M1") (pin "1") (pinfunction "V+_1") (pintype "bidirectional"))
      (node (ref "M2") (pin "1") (pinfunction "V+_1") (pintype "bidirectional"))
      (node (ref "M3") (pin "1") (pinfunction "V+_1") (pintype "bidirectional"))
      (node (ref "M4") (pin "1") (pinfunction "V+_1") (pintype "bidirectional"))
      (node (ref "R11") (pin "2") (pinfunction "2_2") (pintype "passive"))
      (node (ref "R18") (pin "2") (pinfunction "2_2") (pintype "passive"))
      (node (ref "R19") (pin "2") (pinfunction "2_2") (pintype "passive"))
      (node (ref "R20") (pin "2") (pinfunction "2_2") (pintype "passive"))
      (node (ref "R21") (pin "2") (pinfunction "2_2") (pintype "passive"))
      (node (ref "R22") (pin "2") (pinfunction "2_2") (pintype "passive"))
      (node (ref "R26") (pin "2") (pinfunction "2_2") (pintype "passive"))
      (node (ref "R28") (pin "2") (pinfunction "2_2") (pintype "passive"))
      (node (ref "R8") (pin "2") (pinfunction "2_2") (pintype "passive"))
      (node (ref "S1") (pin "B") (pinfunction "ON_B") (pintype "bidirectional"))
      (node (ref "VR1") (pin "1") (pinfunction "IN_1") (pintype "input"))
    )
    (net (code "54") (name "unconnected-(J4-Pad2)") (class "Default")
      (node (ref "J4") (pin "2") (pinfunction "2_2") (pintype "passive"))
    )
    (net (code "55") (name "unconnected-(U1-AREF-Pad62)") (class "Default")
      (node (ref "U1") (pin "62") (pinfunction "AREF_62") (pintype "bidirectional"))
    )
    (net (code "56") (name "unconnected-(U1-PB0(SSN{slash}PCINT0)-Pad36)") (class "Default")
      (node (ref "U1") (pin "36") (pinfunction "PB0(SSN/PCINT0)_36") (pintype "bidirectional"))
    )
    (net (code "57") (name "unconnected-(U1-PD2(RXD1{slash}INT2)-Pad27)") (class "Default")
      (node (ref "U1") (pin "27") (pinfunction "PD2(RXD1/INT2)_27") (pintype "bidirectional"))
    )
    (net (code "58") (name "unconnected-(U1-PD3(TXD1{slash}INT3)-Pad28)") (class "Default")
      (node (ref "U1") (pin "28") (pinfunction "PD3(TXD1/INT3)_28") (pintype "bidirectional"))
    )
    (net (code "59") (name "unconnected-(U1-PD4(ICP1)-Pad29)") (class "Default")
      (node (ref "U1") (pin "29") (pinfunction "PD4(ICP1)_29") (pintype "bidirectional"))
    )
    (net (code "60") (name "unconnected-(U1-PD5(XCK1)-Pad30)") (class "Default")
      (node (ref "U1") (pin "30") (pinfunction "PD5(XCK1)_30") (pintype "bidirectional"))
    )
    (net (code "61") (name "unconnected-(U1-PD6(T1)-Pad31)") (class "Default")
      (node (ref "U1") (pin "31") (pinfunction "PD6(T1)_31") (pintype "bidirectional"))
    )
    (net (code "62") (name "unconnected-(U1-PD7(T0)-Pad32)") (class "Default")
      (node (ref "U1") (pin "32") (pinfunction "PD7(T0)_32") (pintype "bidirectional"))
    )
    (net (code "63") (name "unconnected-(U1-PE2(XCK0{slash}AIN0)-Pad48)") (class "Default")
      (node (ref "U1") (pin "48") (pinfunction "PE2(XCK0/AIN0)_48") (pintype "bidirectional"))
    )
    (net (code "64") (name "unconnected-(U1-PE6(T3{slash}INT6)-Pad52)") (class "Default")
      (node (ref "U1") (pin "52") (pinfunction "PE6(T3/INT6)_52") (pintype "bidirectional"))
    )
    (net (code "65") (name "unconnected-(U1-PE7(ICP3{slash}INT7{slash}CLKO)-Pad53)") (class "Default")
      (node (ref "U1") (pin "53") (pinfunction "PE7(ICP3/INT7/CLKO)_53") (pintype "bidirectional"))
    )
    (net (code "66") (name "unconnected-(U1-PF1(ADC1)-Pad64)") (class "Default")
      (node (ref "U1") (pin "64") (pinfunction "PF1(ADC1)_64") (pintype "bidirectional"))
    )
    (net (code "67") (name "unconnected-(U1-PF2(ADC2{slash}DIG2)-Pad1)") (class "Default")
      (node (ref "U1") (pin "1") (pinfunction "PF2(ADC2/DIG2)_1") (pintype "bidirectional"))
    )
    (net (code "68") (name "unconnected-(U1-PF3(ADC3{slash}DIG4)-Pad2)") (class "Default")
      (node (ref "U1") (pin "2") (pinfunction "PF3(ADC3/DIG4)_2") (pintype "bidirectional"))
    )
    (net (code "69") (name "unconnected-(U1-PF4(ADC4{slash}TCK)-Pad3)") (class "Default")
      (node (ref "U1") (pin "3") (pinfunction "PF4(ADC4/TCK)_3") (pintype "bidirectional"))
    )
    (net (code "70") (name "unconnected-(U1-PF5(ADC5{slash}TMS)-Pad4)") (class "Default")
      (node (ref "U1") (pin "4") (pinfunction "PF5(ADC5/TMS)_4") (pintype "bidirectional"))
    )
    (net (code "71") (name "unconnected-(U1-PF6(ADC6{slash}TDO)-Pad5)") (class "Default")
      (node (ref "U1") (pin "5") (pinfunction "PF6(ADC6/TDO)_5") (pintype "bidirectional"))
    )
    (net (code "72") (name "unconnected-(U1-PF7(ADC7{slash}TDI)-Pad6)") (class "Default")
      (node (ref "U1") (pin "6") (pinfunction "PF7(ADC7/TDI)_6") (pintype "bidirectional"))
    )
    (net (code "73") (name "unconnected-(U1-PG2(AMR)-Pad16)") (class "Default")
      (node (ref "U1") (pin "16") (pinfunction "PG2(AMR)_16") (pintype "bidirectional"))
    )
    (net (code "74") (name "unconnected-(U1-PG3(TOSC2)-Pad17)") (class "Default")
      (node (ref "U1") (pin "17") (pinfunction "PG3(TOSC2)_17") (pintype "bidirectional"))
    )
    (net (code "75") (name "unconnected-(U1-PG4(TOSC1)-Pad18)") (class "Default")
      (node (ref "U1") (pin "18") (pinfunction "PG4(TOSC1)_18") (pintype "bidirectional"))
    )
    (net (code "76") (name "unconnected-(U1-RSTON-Pad13)") (class "Default")
      (node (ref "U1") (pin "13") (pinfunction "RSTON_13") (pintype "bidirectional"))
    )
    (net (code "77") (name "unconnected-(U2-PadDRDY_M)") (class "Default")
      (node (ref "U2") (pin "DRDY_M") (pinfunction "DRDY_M_DRDY_M") (pintype "bidirectional"))
    )
    (net (code "78") (name "unconnected-(U2-PadINT1_A{slash}G)") (class "Default")
      (node (ref "U2") (pin "INT1_A/G") (pinfunction "INT1_A/G_INT1_A/G") (pintype "bidirectional"))
    )
    (net (code "79") (name "unconnected-(U2-PadINT2_A{slash}G)") (class "Default")
      (node (ref "U2") (pin "INT2_A/G") (pinfunction "INT2_A/G_INT2_A/G") (pintype "bidirectional"))
    )
    (net (code "80") (name "unconnected-(U2-PadINT_M)") (class "Default")
      (node (ref "U2") (pin "INT_M") (pinfunction "INT_M_INT_M") (pintype "bidirectional"))
    )
    (net (code "81") (name "unconnected-(VR1-NC{slash}FB-Pad4)") (class "Default")
      (node (ref "VR1") (pin "4") (pinfunction "NC/FB_4") (pintype "passive"))
    )
  )
)
